# Arduino_Shields.net
KiCad netlist of a schematic drawn in Altium Designer
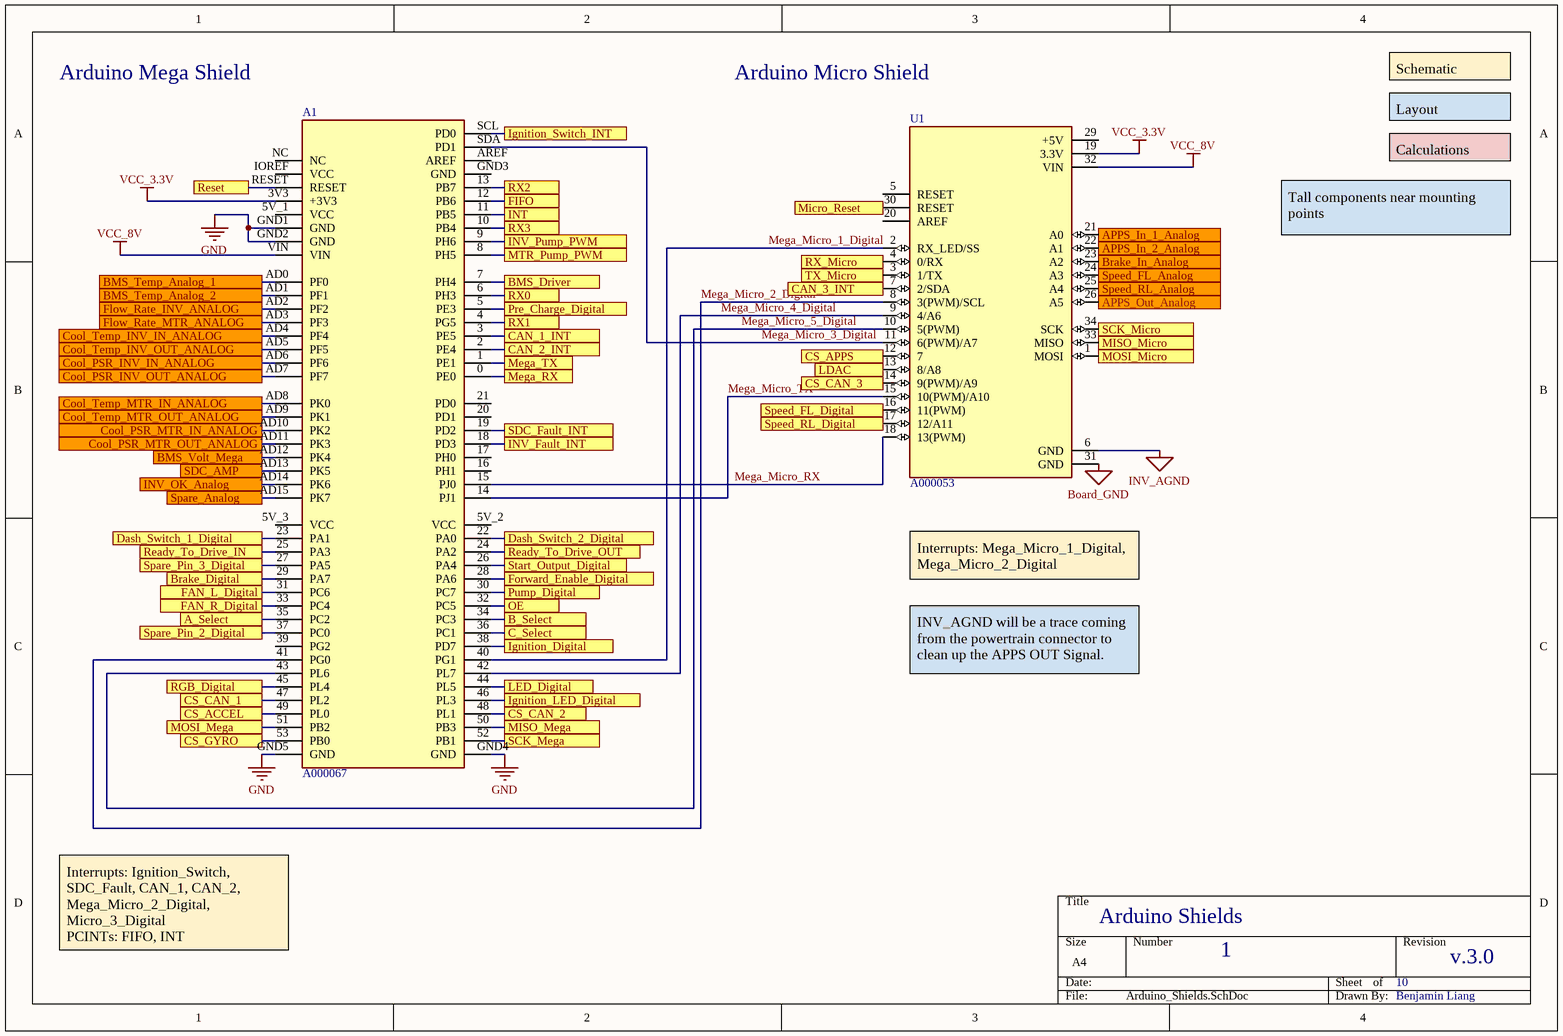
[diagram p0: Arduino_Shields.SchDoc]

(export (version "E")
  (design (tool "Eeschema 10.0.6"))
  (components
    (comp (ref "A1")
      (value "A000067")
      (footprint "SnapEDApcb:ARDUINO_A000067")
      (description "ATmega2560 Arduino Mega2560 AVRÂ® ATmega AVR MCU 8-Bit Embedded Evaluation Board")
      (fields (field (name "MF") "Arduino"))
      (libsource (lib "SnapEDAsch") (part "A000067"))
    )
    (comp (ref "U1")
      (value "A000053")
      (footprint "ARDUINO_A000053")
      (description "ATmega32U4 Arduino Micro AVRÂ® ATmega AVR MCU 8-Bit Embedded Evaluation Board")
      (fields (field (name "DIGI-KEY_PART_NUMBER") "1050-1066-ND") (field (name "MF") "Arduino"))
      (libsource (lib "SnapEDAsch") (part "A000053"))
    )
  )
  (nets
    (net (code "1") (name "/APPS_In_1_Analog") (class "Default")
      (node (ref "U1") (pin "21") (pinfunction "A0_21") (pintype "bidirectional"))
    )
    (net (code "2") (name "/APPS_In_2_Analog") (class "Default")
      (node (ref "U1") (pin "22") (pinfunction "A1_22") (pintype "bidirectional"))
    )
    (net (code "3") (name "/APPS_Out_Analog") (class "Default")
      (node (ref "U1") (pin "26") (pinfunction "A5_26") (pintype "bidirectional"))
    )
    (net (code "4") (name "/A_Select") (class "Default")
      (node (ref "A1") (pin "35") (pinfunction "PC2_35") (pintype "passive"))
    )
    (net (code "5") (name "/BMS_Driver") (class "Default")
      (node (ref "A1") (pin "7") (pinfunction "PH4_7") (pintype "passive"))
    )
    (net (code "6") (name "/BMS_Temp_Analog_1") (class "Default")
      (node (ref "A1") (pin "AD0") (pinfunction "PF0_AD0") (pintype "passive"))
    )
    (net (code "7") (name "/BMS_Temp_Analog_2") (class "Default")
      (node (ref "A1") (pin "AD1") (pinfunction "PF1_AD1") (pintype "passive"))
    )
    (net (code "8") (name "/BMS_Volt_Mega") (class "Default")
      (node (ref "A1") (pin "AD12") (pinfunction "PK4_AD12") (pintype "passive"))
    )
    (net (code "9") (name "/B_Select") (class "Default")
      (node (ref "A1") (pin "34") (pinfunction "PC3_34") (pintype "passive"))
    )
    (net (code "10") (name "/Brake_Digital") (class "Default")
      (node (ref "A1") (pin "29") (pinfunction "PA7_29") (pintype "passive"))
    )
    (net (code "11") (name "/Brake_In_Analog") (class "Default")
      (node (ref "U1") (pin "23") (pinfunction "A2_23") (pintype "bidirectional"))
    )
    (net (code "12") (name "/CAN_1_INT") (class "Default")
      (node (ref "A1") (pin "3") (pinfunction "PE5_3") (pintype "passive"))
    )
    (net (code "13") (name "/CAN_2_INT") (class "Default")
      (node (ref "A1") (pin "2") (pinfunction "PE4_2") (pintype "passive"))
    )
    (net (code "14") (name "/CAN_3_INT") (class "Default")
      (node (ref "U1") (pin "7") (pinfunction "2/SDA_7") (pintype "bidirectional"))
    )
    (net (code "15") (name "/CS_ACCEL") (class "Default")
      (node (ref "A1") (pin "49") (pinfunction "PL0_49") (pintype "passive"))
    )
    (net (code "16") (name "/CS_APPS") (class "Default")
      (node (ref "U1") (pin "12") (pinfunction "7_12") (pintype "bidirectional"))
    )
    (net (code "17") (name "/CS_CAN_1") (class "Default")
      (node (ref "A1") (pin "47") (pinfunction "PL2_47") (pintype "passive"))
    )
    (net (code "18") (name "/CS_CAN_2") (class "Default")
      (node (ref "A1") (pin "48") (pinfunction "PL1_48") (pintype "passive"))
    )
    (net (code "19") (name "/CS_CAN_3") (class "Default")
      (node (ref "U1") (pin "14") (pinfunction "9(PWM)/A9_14") (pintype "bidirectional"))
    )
    (net (code "20") (name "/CS_GYRO") (class "Default")
      (node (ref "A1") (pin "53") (pinfunction "PB0_53") (pintype "passive"))
    )
    (net (code "21") (name "/C_Select") (class "Default")
      (node (ref "A1") (pin "36") (pinfunction "PC1_36") (pintype "passive"))
    )
    (net (code "22") (name "/Cool_PSR_INV_IN_ANALOG") (class "Default")
      (node (ref "A1") (pin "AD6") (pinfunction "PF6_AD6") (pintype "passive"))
    )
    (net (code "23") (name "/Cool_PSR_INV_OUT_ANALOG") (class "Default")
      (node (ref "A1") (pin "AD7") (pinfunction "PF7_AD7") (pintype "passive"))
    )
    (net (code "24") (name "/Cool_PSR_MTR_IN_ANALOG") (class "Default")
      (node (ref "A1") (pin "AD10") (pinfunction "PK2_AD10") (pintype "passive"))
    )
    (net (code "25") (name "/Cool_PSR_MTR_OUT_ANALOG") (class "Default")
      (node (ref "A1") (pin "AD11") (pinfunction "PK3_AD11") (pintype "passive"))
    )
    (net (code "26") (name "/Cool_Temp_INV_IN_ANALOG") (class "Default")
      (node (ref "A1") (pin "AD4") (pinfunction "PF4_AD4") (pintype "passive"))
    )
    (net (code "27") (name "/Cool_Temp_INV_OUT_ANALOG") (class "Default")
      (node (ref "A1") (pin "AD5") (pinfunction "PF5_AD5") (pintype "passive"))
    )
    (net (code "28") (name "/Cool_Temp_MTR_IN_ANALOG") (class "Default")
      (node (ref "A1") (pin "AD8") (pinfunction "PK0_AD8") (pintype "passive"))
    )
    (net (code "29") (name "/Cool_Temp_MTR_OUT_ANALOG") (class "Default")
      (node (ref "A1") (pin "AD9") (pinfunction "PK1_AD9") (pintype "passive"))
    )
    (net (code "30") (name "/Dash_Switch_1_Digital") (class "Default")
      (node (ref "A1") (pin "23") (pinfunction "PA1_23") (pintype "passive"))
    )
    (net (code "31") (name "/Dash_Switch_2_Digital") (class "Default")
      (node (ref "A1") (pin "22") (pinfunction "PA0_22") (pintype "passive"))
    )
    (net (code "32") (name "/FAN_L_Digital") (class "Default")
      (node (ref "A1") (pin "31") (pinfunction "PC6_31") (pintype "passive"))
    )
    (net (code "33") (name "/FAN_R_Digital") (class "Default")
      (node (ref "A1") (pin "33") (pinfunction "PC4_33") (pintype "passive"))
    )
    (net (code "34") (name "/FIFO") (class "Default")
      (node (ref "A1") (pin "12") (pinfunction "PB6_12") (pintype "passive"))
    )
    (net (code "35") (name "/Flow_Rate_INV_ANALOG") (class "Default")
      (node (ref "A1") (pin "AD2") (pinfunction "PF2_AD2") (pintype "passive"))
    )
    (net (code "36") (name "/Flow_Rate_MTR_ANALOG") (class "Default")
      (node (ref "A1") (pin "AD3") (pinfunction "PF3_AD3") (pintype "passive"))
    )
    (net (code "37") (name "/Forward_Enable_Digital") (class "Default")
      (node (ref "A1") (pin "28") (pinfunction "PA6_28") (pintype "passive"))
    )
    (net (code "38") (name "/INT") (class "Default")
      (node (ref "A1") (pin "11") (pinfunction "PB5_11") (pintype "passive"))
    )
    (net (code "39") (name "/INV_Fault_INT") (class "Default")
      (node (ref "A1") (pin "18") (pinfunction "PD3_18") (pintype "passive"))
    )
    (net (code "40") (name "/INV_OK_Analog") (class "Default")
      (node (ref "A1") (pin "AD14") (pinfunction "PK6_AD14") (pintype "passive"))
    )
    (net (code "41") (name "/INV_Pump_PWM") (class "Default")
      (node (ref "A1") (pin "9") (pinfunction "PH6_9") (pintype "passive"))
    )
    (net (code "42") (name "/Ignition_Digital") (class "Default")
      (node (ref "A1") (pin "38") (pinfunction "PD7_38") (pintype "passive"))
    )
    (net (code "43") (name "/Ignition_LED_Digital") (class "Default")
      (node (ref "A1") (pin "46") (pinfunction "PL3_46") (pintype "passive"))
    )
    (net (code "44") (name "/Ignition_Switch_INT") (class "Default")
      (node (ref "A1") (pin "SCL") (pinfunction "PD0_SCL") (pintype "passive"))
    )
    (net (code "45") (name "/LDAC") (class "Default")
      (node (ref "U1") (pin "13") (pinfunction "8/A8_13") (pintype "bidirectional"))
    )
    (net (code "46") (name "/LED_Digital") (class "Default")
      (node (ref "A1") (pin "44") (pinfunction "PL5_44") (pintype "passive"))
    )
    (net (code "47") (name "/MISO_Mega") (class "Default")
      (node (ref "A1") (pin "50") (pinfunction "PB3_50") (pintype "passive"))
    )
    (net (code "48") (name "/MISO_Micro") (class "Default")
      (node (ref "U1") (pin "33") (pinfunction "MISO_33") (pintype "bidirectional"))
    )
    (net (code "49") (name "/MOSI_Mega") (class "Default")
      (node (ref "A1") (pin "51") (pinfunction "PB2_51") (pintype "passive"))
    )
    (net (code "50") (name "/MOSI_Micro") (class "Default")
      (node (ref "U1") (pin "1") (pinfunction "MOSI_1") (pintype "bidirectional"))
    )
    (net (code "51") (name "/MTR_Pump_PWM") (class "Default")
      (node (ref "A1") (pin "8") (pinfunction "PH5_8") (pintype "passive"))
    )
    (net (code "52") (name "/Mega_Micro_1_Digital") (class "Default")
      (node (ref "A1") (pin "40") (pinfunction "PG1_40") (pintype "passive"))
      (node (ref "U1") (pin "2") (pinfunction "RX_LED/SS_2") (pintype "bidirectional"))
    )
    (net (code "53") (name "/Mega_Micro_2_Digital") (class "Default")
      (node (ref "A1") (pin "41") (pinfunction "PG0_41") (pintype "passive"))
      (node (ref "U1") (pin "8") (pinfunction "3(PWM)/SCL_8") (pintype "bidirectional"))
    )
    (net (code "54") (name "/Mega_Micro_3_Digital") (class "Default")
      (node (ref "A1") (pin "SDA") (pinfunction "PD1_SDA") (pintype "passive"))
      (node (ref "U1") (pin "11") (pinfunction "6(PWM)/A7_11") (pintype "bidirectional"))
    )
    (net (code "55") (name "/Mega_Micro_4_Digital") (class "Default")
      (node (ref "A1") (pin "42") (pinfunction "PL7_42") (pintype "passive"))
      (node (ref "U1") (pin "9") (pinfunction "4/A6_9") (pintype "bidirectional"))
    )
    (net (code "56") (name "/Mega_Micro_5_Digital") (class "Default")
      (node (ref "A1") (pin "43") (pinfunction "PL6_43") (pintype "passive"))
      (node (ref "U1") (pin "10") (pinfunction "5(PWM)_10") (pintype "bidirectional"))
    )
    (net (code "57") (name "/Mega_Micro_RX") (class "Default")
      (node (ref "A1") (pin "15") (pinfunction "PJ0_15") (pintype "passive"))
      (node (ref "U1") (pin "18") (pinfunction "13(PWM)_18") (pintype "bidirectional"))
    )
    (net (code "58") (name "/Mega_Micro_TX") (class "Default")
      (node (ref "A1") (pin "14") (pinfunction "PJ1_14") (pintype "passive"))
      (node (ref "U1") (pin "15") (pinfunction "10(PWM)/A10_15") (pintype "bidirectional"))
    )
    (net (code "59") (name "/Mega_RX") (class "Default")
      (node (ref "A1") (pin "0") (pinfunction "PE0_0") (pintype "passive"))
    )
    (net (code "60") (name "/Mega_TX") (class "Default")
      (node (ref "A1") (pin "1") (pinfunction "PE1_1") (pintype "passive"))
    )
    (net (code "61") (name "/Micro_Reset") (class "Default")
      (node (ref "U1") (pin "30") (pinfunction "RESET_30") (pintype "passive"))
    )
    (net (code "62") (name "/OE") (class "Default")
      (node (ref "A1") (pin "32") (pinfunction "PC5_32") (pintype "passive"))
    )
    (net (code "63") (name "/Pre_Charge_Digital") (class "Default")
      (node (ref "A1") (pin "5") (pinfunction "PE3_5") (pintype "passive"))
    )
    (net (code "64") (name "/Pump_Digital") (class "Default")
      (node (ref "A1") (pin "30") (pinfunction "PC7_30") (pintype "passive"))
    )
    (net (code "65") (name "/RGB_Digital") (class "Default")
      (node (ref "A1") (pin "45") (pinfunction "PL4_45") (pintype "passive"))
    )
    (net (code "66") (name "/RX0") (class "Default")
      (node (ref "A1") (pin "6") (pinfunction "PH3_6") (pintype "passive"))
    )
    (net (code "67") (name "/RX1") (class "Default")
      (node (ref "A1") (pin "4") (pinfunction "PG5_4") (pintype "passive"))
    )
    (net (code "68") (name "/RX2") (class "Default")
      (node (ref "A1") (pin "13") (pinfunction "PB7_13") (pintype "passive"))
    )
    (net (code "69") (name "/RX3") (class "Default")
      (node (ref "A1") (pin "10") (pinfunction "PB4_10") (pintype "passive"))
    )
    (net (code "70") (name "/RX_Micro") (class "Default")
      (node (ref "U1") (pin "4") (pinfunction "0/RX_4") (pintype "bidirectional"))
    )
    (net (code "71") (name "/Ready_To_Drive_IN") (class "Default")
      (node (ref "A1") (pin "25") (pinfunction "PA3_25") (pintype "passive"))
    )
    (net (code "72") (name "/Ready_To_Drive_OUT") (class "Default")
      (node (ref "A1") (pin "24") (pinfunction "PA2_24") (pintype "passive"))
    )
    (net (code "73") (name "/Reset") (class "Default")
      (node (ref "A1") (pin "RESET") (pinfunction "RESET_RESET") (pintype "passive"))
    )
    (net (code "74") (name "/SCK_Mega") (class "Default")
      (node (ref "A1") (pin "52") (pinfunction "PB1_52") (pintype "passive"))
    )
    (net (code "75") (name "/SCK_Micro") (class "Default")
      (node (ref "U1") (pin "34") (pinfunction "SCK_34") (pintype "bidirectional"))
    )
    (net (code "76") (name "/SDC_AMP") (class "Default")
      (node (ref "A1") (pin "AD13") (pinfunction "PK5_AD13") (pintype "passive"))
    )
    (net (code "77") (name "/SDC_Fault_INT") (class "Default")
      (node (ref "A1") (pin "19") (pinfunction "PD2_19") (pintype "passive"))
    )
    (net (code "78") (name "/Spare_Analog") (class "Default")
      (node (ref "A1") (pin "AD15") (pinfunction "PK7_AD15") (pintype "passive"))
    )
    (net (code "79") (name "/Spare_Pin_2_Digital") (class "Default")
      (node (ref "A1") (pin "37") (pinfunction "PC0_37") (pintype "passive"))
    )
    (net (code "80") (name "/Spare_Pin_3_Digital") (class "Default")
      (node (ref "A1") (pin "27") (pinfunction "PA5_27") (pintype "passive"))
    )
    (net (code "81") (name "/Speed_FL_Analog") (class "Default")
      (node (ref "U1") (pin "24") (pinfunction "A3_24") (pintype "bidirectional"))
    )
    (net (code "82") (name "/Speed_FL_Digital") (class "Default")
      (node (ref "U1") (pin "16") (pinfunction "11(PWM)_16") (pintype "bidirectional"))
    )
    (net (code "83") (name "/Speed_RL_Analog") (class "Default")
      (node (ref "U1") (pin "25") (pinfunction "A4_25") (pintype "bidirectional"))
    )
    (net (code "84") (name "/Speed_RL_Digital") (class "Default")
      (node (ref "U1") (pin "17") (pinfunction "12/A11_17") (pintype "bidirectional"))
    )
    (net (code "85") (name "/Start_Output_Digital") (class "Default")
      (node (ref "A1") (pin "26") (pinfunction "PA4_26") (pintype "passive"))
    )
    (net (code "86") (name "/TX_Micro") (class "Default")
      (node (ref "U1") (pin "3") (pinfunction "1/TX_3") (pintype "bidirectional"))
    )
    (net (code "87") (name "Board_GND") (class "Default")
      (node (ref "U1") (pin "31") (pinfunction "GND_31") (pintype "power_in"))
    )
    (net (code "88") (name "GND") (class "Default")
      (node (ref "A1") (pin "GND1") (pinfunction "GND_GND1") (pintype "passive"))
      (node (ref "A1") (pin "GND2") (pinfunction "GND_GND2") (pintype "passive"))
      (node (ref "A1") (pin "GND4") (pinfunction "GND_GND4") (pintype "passive"))
      (node (ref "A1") (pin "GND5") (pinfunction "GND_GND5") (pintype "passive"))
    )
    (net (code "89") (name "INV_AGND") (class "Default")
      (node (ref "U1") (pin "6") (pinfunction "GND_6") (pintype "power_in"))
    )
    (net (code "90") (name "VCC_3.3V") (class "Default")
      (node (ref "A1") (pin "3V3") (pinfunction "+3V3_3V3") (pintype "passive"))
      (node (ref "U1") (pin "19") (pinfunction "3.3V_19") (pintype "power_in"))
    )
    (net (code "91") (name "VCC_8V") (class "Default")
      (node (ref "A1") (pin "VIN") (pinfunction "VIN_VIN") (pintype "passive"))
      (node (ref "U1") (pin "32") (pinfunction "VIN_32") (pintype "power_in"))
    )
    (net (code "92") (name "unconnected-(A1-GND-PadGND3)") (class "Default")
      (node (ref "A1") (pin "GND3") (pinfunction "GND_GND3") (pintype "passive"))
    )
    (net (code "93") (name "unconnected-(A1-PD0-Pad21)") (class "Default")
      (node (ref "A1") (pin "21") (pinfunction "PD0_21") (pintype "passive"))
    )
    (net (code "94") (name "unconnected-(A1-PD1-Pad20)") (class "Default")
      (node (ref "A1") (pin "20") (pinfunction "PD1_20") (pintype "passive"))
    )
    (net (code "95") (name "unconnected-(A1-PG2-Pad39)") (class "Default")
      (node (ref "A1") (pin "39") (pinfunction "PG2_39") (pintype "passive"))
    )
    (net (code "96") (name "unconnected-(A1-PH0-Pad17)") (class "Default")
      (node (ref "A1") (pin "17") (pinfunction "PH0_17") (pintype "passive"))
    )
    (net (code "97") (name "unconnected-(A1-PH1-Pad16)") (class "Default")
      (node (ref "A1") (pin "16") (pinfunction "PH1_16") (pintype "passive"))
    )
    (net (code "98") (name "unconnected-(A1-PadAREF)") (class "Default")
      (node (ref "A1") (pin "AREF") (pinfunction "AREF_AREF") (pintype "passive"))
    )
    (net (code "99") (name "unconnected-(A1-PadNC)") (class "Default")
      (node (ref "A1") (pin "NC") (pinfunction "NC_NC") (pintype "passive"))
    )
    (net (code "100") (name "unconnected-(A1-VCC-Pad5V_1)") (class "Default")
      (node (ref "A1") (pin "5V_1") (pinfunction "VCC_5V_1") (pintype "passive"))
    )
    (net (code "101") (name "unconnected-(A1-VCC-Pad5V_2)") (class "Default")
      (node (ref "A1") (pin "5V_2") (pinfunction "VCC_5V_2") (pintype "passive"))
    )
    (net (code "102") (name "unconnected-(A1-VCC-Pad5V_3)") (class "Default")
      (node (ref "A1") (pin "5V_3") (pinfunction "VCC_5V_3") (pintype "passive"))
    )
    (net (code "103") (name "unconnected-(A1-VCC-PadIOREF)") (class "Default")
      (node (ref "A1") (pin "IOREF") (pinfunction "VCC_IOREF") (pintype "passive"))
    )
    (net (code "104") (name "unconnected-(U1-+5V-Pad29)") (class "Default")
      (node (ref "U1") (pin "29") (pinfunction "+5V_29") (pintype "power_in"))
    )
    (net (code "105") (name "unconnected-(U1-AREF-Pad20)") (class "Default")
      (node (ref "U1") (pin "20") (pinfunction "AREF_20") (pintype "passive"))
    )
    (net (code "106") (name "unconnected-(U1-RESET-Pad5)") (class "Default")
      (node (ref "U1") (pin "5") (pinfunction "RESET_5") (pintype "passive"))
    )
  )
)
